# PROC051D_HD_Connector.net
KiCad netlist of a schematic drawn in Altium Designer
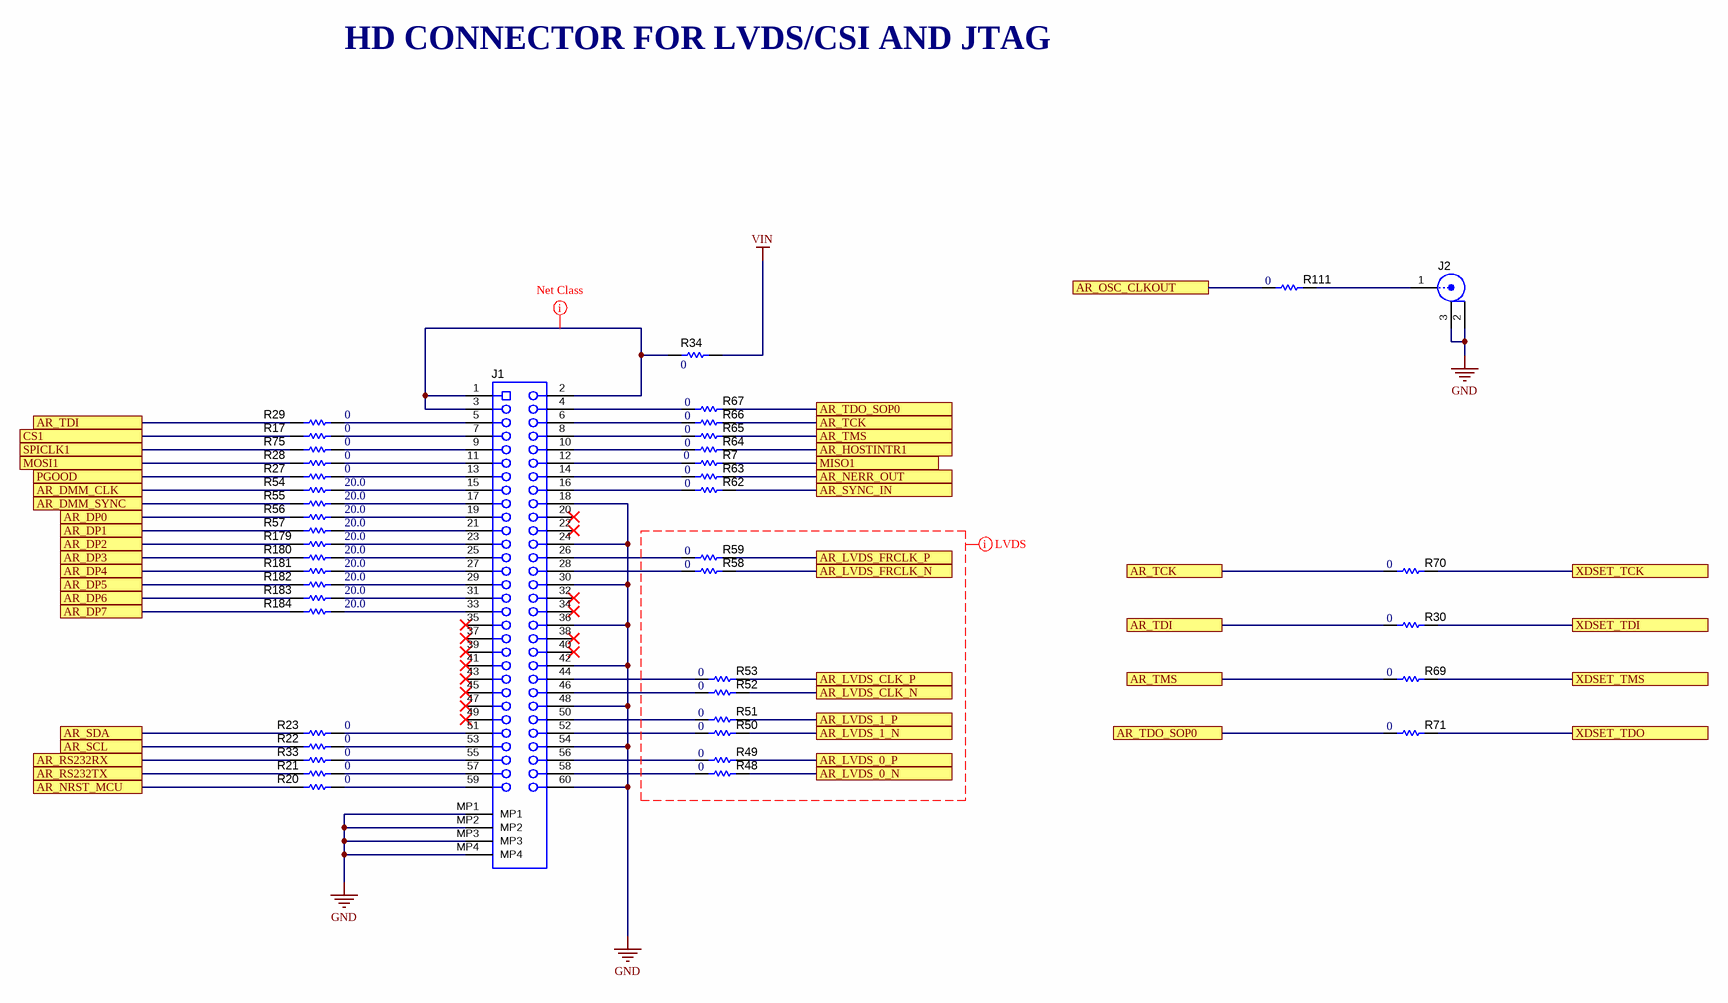
[diagram p0: PROC051D_HD Connector.SchDoc]

(export (version "E")
  (design (tool "Eeschema 10.0.6"))
  (components
    (comp (ref "J1")
      (value "QSH-030-01-L-D-A")
      (footprint "Samtec_QSH-030-01-X-D-A")
      (description "Receptacle, 0.5 mm, 30x2, Gold, TH")
      (fields (field (name "MANUFACTURER") "Samtec") (field (name "PUBLISHER") "Texas Instruments"))
      (libsource (lib "Altium Vault - TI") (part "CMP-0075524-1"))
    )
    (comp (ref "J2")
      (value "128-0711-201")
      (footprint "Johnson_128-0711-201")
      (description "UMC Straight Jack Receptacle, 50 Ohm, Gold, SMT")
      (fields
        (field (name "MANUFACTURER") "Cinch Connectivity")
        (field (name "PUBLISHER") "Texas Instruments")
      )
      (libsource (lib "Altium Vault - TI") (part "CMP-0055788-1"))
    )
    (comp (ref "R7")
      (value "CRCW02010000Z0ED")
      (footprint "0201_Silk")
      (description "RES, 0, 5%, 0.05 W, 0201")
      (fields (field (name "MANUFACTURER") "Vishay-Dale") (field (name "VALUEDISPLAYED") "0"))
      (libsource (lib "Altium Vault - TI") (part "Resistor"))
    )
    (comp (ref "R17")
      (value "CRCW02010000Z0ED")
      (footprint "0201_Silk")
      (description "RES, 0, 5%, 0.05 W, 0201")
      (fields (field (name "MANUFACTURER") "Vishay-Dale") (field (name "VALUEDISPLAYED") "0"))
      (libsource (lib "Altium Vault - TI") (part "Resistor"))
    )
    (comp (ref "R20")
      (value "CRCW02010000Z0ED")
      (footprint "0201_Silk")
      (description "RES, 0, 5%, 0.05 W, 0201")
      (fields (field (name "MANUFACTURER") "Vishay-Dale") (field (name "VALUEDISPLAYED") "0"))
      (libsource (lib "Altium Vault - TI") (part "Resistor"))
    )
    (comp (ref "R21")
      (value "CRCW02010000Z0ED")
      (footprint "0201_Silk")
      (description "RES, 0, 5%, 0.05 W, 0201")
      (fields (field (name "MANUFACTURER") "Vishay-Dale") (field (name "VALUEDISPLAYED") "0"))
      (libsource (lib "Altium Vault - TI") (part "Resistor"))
    )
    (comp (ref "R22")
      (value "CRCW02010000Z0ED")
      (footprint "0201_Silk")
      (description "RES, 0, 5%, 0.05 W, 0201")
      (fields (field (name "MANUFACTURER") "Vishay-Dale") (field (name "VALUEDISPLAYED") "0"))
      (libsource (lib "Altium Vault - TI") (part "Resistor"))
    )
    (comp (ref "R23")
      (value "CRCW02010000Z0ED")
      (footprint "0201_Silk")
      (description "RES, 0, 5%, 0.05 W, 0201")
      (fields (field (name "MANUFACTURER") "Vishay-Dale") (field (name "VALUEDISPLAYED") "0"))
      (libsource (lib "Altium Vault - TI") (part "Resistor"))
    )
    (comp (ref "R27")
      (value "CRCW02010000Z0ED")
      (footprint "0201_Silk")
      (description "RES, 0, 5%, 0.05 W, 0201")
      (fields (field (name "MANUFACTURER") "Vishay-Dale") (field (name "VALUEDISPLAYED") "0"))
      (libsource (lib "Altium Vault - TI") (part "Resistor"))
    )
    (comp (ref "R28")
      (value "CRCW02010000Z0ED")
      (footprint "0201_Silk")
      (description "RES, 0, 5%, 0.05 W, 0201")
      (fields (field (name "MANUFACTURER") "Vishay-Dale") (field (name "VALUEDISPLAYED") "0"))
      (libsource (lib "Altium Vault - TI") (part "Resistor"))
    )
    (comp (ref "R29")
      (value "CRCW02010000Z0ED")
      (footprint "0201_Silk")
      (description "RES, 0, 5%, 0.05 W, 0201")
      (fields (field (name "MANUFACTURER") "Vishay-Dale") (field (name "VALUEDISPLAYED") "0"))
      (libsource (lib "Altium Vault - TI") (part "Resistor"))
    )
    (comp (ref "R30")
      (value "CRCW02010000Z0ED")
      (footprint "0201_Silk")
      (description "RES, 0, 5%, 0.05 W, 0201")
      (fields (field (name "MANUFACTURER") "Vishay-Dale") (field (name "VALUEDISPLAYED") "0"))
      (libsource (lib "Altium Vault - TI") (part "Resistor"))
    )
    (comp (ref "R33")
      (value "CRCW02010000Z0ED")
      (footprint "0201_Silk")
      (description "RES, 0, 5%, 0.05 W, 0201")
      (fields (field (name "MANUFACTURER") "Vishay-Dale") (field (name "VALUEDISPLAYED") "0"))
      (libsource (lib "Altium Vault - TI") (part "Resistor"))
    )
    (comp (ref "R34")
      (value "CRCW20100000Z0EF")
      (footprint "2010")
      (description "RES, 0, 5%, 0.75 W, AEC-Q200 Grade 0, 2010")
      (fields (field (name "MANUFACTURER") "Vishay-Dale") (field (name "VALUEDISPLAYED") "0"))
      (libsource (lib "Altium Vault - TI") (part "Resistor"))
    )
    (comp (ref "R48")
      (value "CRCW02010000Z0ED")
      (footprint "0201_Silk")
      (description "RES, 0, 5%, 0.05 W, 0201")
      (fields (field (name "MANUFACTURER") "Vishay-Dale") (field (name "VALUEDISPLAYED") "0"))
      (libsource (lib "Altium Vault - TI") (part "Resistor"))
    )
    (comp (ref "R49")
      (value "CRCW02010000Z0ED")
      (footprint "0201_Silk")
      (description "RES, 0, 5%, 0.05 W, 0201")
      (fields (field (name "MANUFACTURER") "Vishay-Dale") (field (name "VALUEDISPLAYED") "0"))
      (libsource (lib "Altium Vault - TI") (part "Resistor"))
    )
    (comp (ref "R50")
      (value "CRCW02010000Z0ED")
      (footprint "0201_Silk")
      (description "RES, 0, 5%, 0.05 W, 0201")
      (fields (field (name "MANUFACTURER") "Vishay-Dale") (field (name "VALUEDISPLAYED") "0"))
      (libsource (lib "Altium Vault - TI") (part "Resistor"))
    )
    (comp (ref "R51")
      (value "CRCW02010000Z0ED")
      (footprint "0201_Silk")
      (description "RES, 0, 5%, 0.05 W, 0201")
      (fields (field (name "MANUFACTURER") "Vishay-Dale") (field (name "VALUEDISPLAYED") "0"))
      (libsource (lib "Altium Vault - TI") (part "Resistor"))
    )
    (comp (ref "R52")
      (value "CRCW02010000Z0ED")
      (footprint "0201_Silk")
      (description "RES, 0, 5%, 0.05 W, 0201")
      (fields (field (name "MANUFACTURER") "Vishay-Dale") (field (name "VALUEDISPLAYED") "0"))
      (libsource (lib "Altium Vault - TI") (part "Resistor"))
    )
    (comp (ref "R53")
      (value "CRCW02010000Z0ED")
      (footprint "0201_Silk")
      (description "RES, 0, 5%, 0.05 W, 0201")
      (fields (field (name "MANUFACTURER") "Vishay-Dale") (field (name "VALUEDISPLAYED") "0"))
      (libsource (lib "Altium Vault - TI") (part "Resistor"))
    )
    (comp (ref "R54")
      (value "CRCW020120R0FNED")
      (footprint "0201_033")
      (description "RES, 20.0, 1%, 0.05 W, 0201")
      (fields (field (name "MANUFACTURER") "Vishay-Dale") (field (name "VALUEDISPLAYED") "20.0"))
      (libsource (lib "Altium Vault - TI") (part "Resistor"))
    )
    (comp (ref "R55")
      (value "CRCW020120R0FNED")
      (footprint "0201_033")
      (description "RES, 20.0, 1%, 0.05 W, 0201")
      (fields (field (name "MANUFACTURER") "Vishay-Dale") (field (name "VALUEDISPLAYED") "20.0"))
      (libsource (lib "Altium Vault - TI") (part "Resistor"))
    )
    (comp (ref "R56")
      (value "CRCW020120R0FNED")
      (footprint "0201_033")
      (description "RES, 20.0, 1%, 0.05 W, 0201")
      (fields (field (name "MANUFACTURER") "Vishay-Dale") (field (name "VALUEDISPLAYED") "20.0"))
      (libsource (lib "Altium Vault - TI") (part "Resistor"))
    )
    (comp (ref "R57")
      (value "CRCW020120R0FNED")
      (footprint "0201_033")
      (description "RES, 20.0, 1%, 0.05 W, 0201")
      (fields (field (name "MANUFACTURER") "Vishay-Dale") (field (name "VALUEDISPLAYED") "20.0"))
      (libsource (lib "Altium Vault - TI") (part "Resistor"))
    )
    (comp (ref "R58")
      (value "CRCW02010000Z0ED")
      (footprint "0201_Silk")
      (description "RES, 0, 5%, 0.05 W, 0201")
      (fields (field (name "MANUFACTURER") "Vishay-Dale") (field (name "VALUEDISPLAYED") "0"))
      (libsource (lib "Altium Vault - TI") (part "Resistor"))
    )
    (comp (ref "R59")
      (value "CRCW02010000Z0ED")
      (footprint "0201_Silk")
      (description "RES, 0, 5%, 0.05 W, 0201")
      (fields (field (name "MANUFACTURER") "Vishay-Dale") (field (name "VALUEDISPLAYED") "0"))
      (libsource (lib "Altium Vault - TI") (part "Resistor"))
    )
    (comp (ref "R62")
      (value "CRCW02010000Z0ED")
      (footprint "0201_Silk")
      (description "RES, 0, 5%, 0.05 W, 0201")
      (fields (field (name "MANUFACTURER") "Vishay-Dale") (field (name "VALUEDISPLAYED") "0"))
      (libsource (lib "Altium Vault - TI") (part "Resistor"))
    )
    (comp (ref "R63")
      (value "CRCW02010000Z0ED")
      (footprint "0201_Silk")
      (description "RES, 0, 5%, 0.05 W, 0201")
      (fields (field (name "MANUFACTURER") "Vishay-Dale") (field (name "VALUEDISPLAYED") "0"))
      (libsource (lib "Altium Vault - TI") (part "Resistor"))
    )
    (comp (ref "R64")
      (value "CRCW02010000Z0ED")
      (footprint "0201_Silk")
      (description "RES, 0, 5%, 0.05 W, 0201")
      (fields (field (name "MANUFACTURER") "Vishay-Dale") (field (name "VALUEDISPLAYED") "0"))
      (libsource (lib "Altium Vault - TI") (part "Resistor"))
    )
    (comp (ref "R65")
      (value "CRCW02010000Z0ED")
      (footprint "0201_Silk")
      (description "RES, 0, 5%, 0.05 W, 0201")
      (fields (field (name "MANUFACTURER") "Vishay-Dale") (field (name "VALUEDISPLAYED") "0"))
      (libsource (lib "Altium Vault - TI") (part "Resistor"))
    )
    (comp (ref "R66")
      (value "CRCW02010000Z0ED")
      (footprint "0201_Silk")
      (description "RES, 0, 5%, 0.05 W, 0201")
      (fields (field (name "MANUFACTURER") "Vishay-Dale") (field (name "VALUEDISPLAYED") "0"))
      (libsource (lib "Altium Vault - TI") (part "Resistor"))
    )
    (comp (ref "R67")
      (value "CRCW02010000Z0ED")
      (footprint "0201_Silk")
      (description "RES, 0, 5%, 0.05 W, 0201")
      (fields (field (name "MANUFACTURER") "Vishay-Dale") (field (name "VALUEDISPLAYED") "0"))
      (libsource (lib "Altium Vault - TI") (part "Resistor"))
    )
    (comp (ref "R69")
      (value "CRCW02010000Z0ED")
      (footprint "0201_Silk")
      (description "RES, 0, 5%, 0.05 W, 0201")
      (fields (field (name "MANUFACTURER") "Vishay-Dale") (field (name "VALUEDISPLAYED") "0"))
      (libsource (lib "Altium Vault - TI") (part "Resistor"))
    )
    (comp (ref "R70")
      (value "CRCW02010000Z0ED")
      (footprint "0201_Silk")
      (description "RES, 0, 5%, 0.05 W, 0201")
      (fields (field (name "MANUFACTURER") "Vishay-Dale") (field (name "VALUEDISPLAYED") "0"))
      (libsource (lib "Altium Vault - TI") (part "Resistor"))
    )
    (comp (ref "R71")
      (value "CRCW02010000Z0ED")
      (footprint "0201_Silk")
      (description "RES, 0, 5%, 0.05 W, 0201")
      (fields (field (name "MANUFACTURER") "Vishay-Dale") (field (name "VALUEDISPLAYED") "0"))
      (libsource (lib "Altium Vault - TI") (part "Resistor"))
    )
    (comp (ref "R75")
      (value "CRCW02010000Z0ED")
      (footprint "0201_Silk")
      (description "RES, 0, 5%, 0.05 W, 0201")
      (fields (field (name "MANUFACTURER") "Vishay-Dale") (field (name "VALUEDISPLAYED") "0"))
      (libsource (lib "Altium Vault - TI") (part "Resistor"))
    )
    (comp (ref "R111")
      (value "CRCW02010000Z0ED")
      (footprint "0201_Silk")
      (description "RES, 0, 5%, 0.05 W, 0201")
      (fields (field (name "MANUFACTURER") "Vishay-Dale") (field (name "VALUEDISPLAYED") "0"))
      (libsource (lib "Altium Vault - TI") (part "Resistor"))
    )
    (comp (ref "R179")
      (value "CRCW020120R0FNED")
      (footprint "0201_033")
      (description "RES, 20.0, 1%, 0.05 W, 0201")
      (fields (field (name "MANUFACTURER") "Vishay-Dale") (field (name "VALUEDISPLAYED") "20.0"))
      (libsource (lib "Altium Vault - TI") (part "Resistor"))
    )
    (comp (ref "R180")
      (value "CRCW020120R0FNED")
      (footprint "0201_033")
      (description "RES, 20.0, 1%, 0.05 W, 0201")
      (fields (field (name "MANUFACTURER") "Vishay-Dale") (field (name "VALUEDISPLAYED") "20.0"))
      (libsource (lib "Altium Vault - TI") (part "Resistor"))
    )
    (comp (ref "R181")
      (value "CRCW020120R0FNED")
      (footprint "0201_033")
      (description "RES, 20.0, 1%, 0.05 W, 0201")
      (fields (field (name "MANUFACTURER") "Vishay-Dale") (field (name "VALUEDISPLAYED") "20.0"))
      (libsource (lib "Altium Vault - TI") (part "Resistor"))
    )
    (comp (ref "R182")
      (value "CRCW020120R0FNED")
      (footprint "0201_033")
      (description "RES, 20.0, 1%, 0.05 W, 0201")
      (fields (field (name "MANUFACTURER") "Vishay-Dale") (field (name "VALUEDISPLAYED") "20.0"))
      (libsource (lib "Altium Vault - TI") (part "Resistor"))
    )
    (comp (ref "R183")
      (value "CRCW020120R0FNED")
      (footprint "0201_033")
      (description "RES, 20.0, 1%, 0.05 W, 0201")
      (fields (field (name "MANUFACTURER") "Vishay-Dale") (field (name "VALUEDISPLAYED") "20.0"))
      (libsource (lib "Altium Vault - TI") (part "Resistor"))
    )
    (comp (ref "R184")
      (value "CRCW020120R0FNED")
      (footprint "0201_033")
      (description "RES, 20.0, 1%, 0.05 W, 0201")
      (fields (field (name "MANUFACTURER") "Vishay-Dale") (field (name "VALUEDISPLAYED") "20.0"))
      (libsource (lib "Altium Vault - TI") (part "Resistor"))
    )
  )
  (nets
    (net (code "1") (name "/AR_DMM_CLK") (class "Default")
      (node (ref "R54") (pin "1") (pinfunction "1_1") (pintype "passive"))
    )
    (net (code "2") (name "/AR_DMM_SYNC") (class "Default")
      (node (ref "R55") (pin "1") (pinfunction "1_1") (pintype "passive"))
    )
    (net (code "3") (name "/AR_DP0") (class "Default")
      (node (ref "R56") (pin "1") (pinfunction "1_1") (pintype "passive"))
    )
    (net (code "4") (name "/AR_DP1") (class "Default")
      (node (ref "R57") (pin "1") (pinfunction "1_1") (pintype "passive"))
    )
    (net (code "5") (name "/AR_DP2") (class "Default")
      (node (ref "R179") (pin "1") (pinfunction "1_1") (pintype "passive"))
    )
    (net (code "6") (name "/AR_DP3") (class "Default")
      (node (ref "R180") (pin "1") (pinfunction "1_1") (pintype "passive"))
    )
    (net (code "7") (name "/AR_DP4") (class "Default")
      (node (ref "R181") (pin "1") (pinfunction "1_1") (pintype "passive"))
    )
    (net (code "8") (name "/AR_DP5") (class "Default")
      (node (ref "R182") (pin "1") (pinfunction "1_1") (pintype "passive"))
    )
    (net (code "9") (name "/AR_DP6") (class "Default")
      (node (ref "R183") (pin "1") (pinfunction "1_1") (pintype "passive"))
    )
    (net (code "10") (name "/AR_DP7") (class "Default")
      (node (ref "R184") (pin "1") (pinfunction "1_1") (pintype "passive"))
    )
    (net (code "11") (name "/AR_HOSTINTR1") (class "Default")
      (node (ref "R64") (pin "2") (pinfunction "2_2") (pintype "passive"))
    )
    (net (code "12") (name "/AR_LVDS_0_N") (class "Default")
      (node (ref "R48") (pin "2") (pinfunction "2_2") (pintype "passive"))
    )
    (net (code "13") (name "/AR_LVDS_0_P") (class "Default")
      (node (ref "R49") (pin "2") (pinfunction "2_2") (pintype "passive"))
    )
    (net (code "14") (name "/AR_LVDS_1_N") (class "Default")
      (node (ref "R50") (pin "2") (pinfunction "2_2") (pintype "passive"))
    )
    (net (code "15") (name "/AR_LVDS_1_P") (class "Default")
      (node (ref "R51") (pin "2") (pinfunction "2_2") (pintype "passive"))
    )
    (net (code "16") (name "/AR_LVDS_CLK_N") (class "Default")
      (node (ref "R52") (pin "2") (pinfunction "2_2") (pintype "passive"))
    )
    (net (code "17") (name "/AR_LVDS_CLK_P") (class "Default")
      (node (ref "R53") (pin "2") (pinfunction "2_2") (pintype "passive"))
    )
    (net (code "18") (name "/AR_LVDS_FRCLK_N") (class "Default")
      (node (ref "R58") (pin "2") (pinfunction "2_2") (pintype "passive"))
    )
    (net (code "19") (name "/AR_LVDS_FRCLK_P") (class "Default")
      (node (ref "R59") (pin "2") (pinfunction "2_2") (pintype "passive"))
    )
    (net (code "20") (name "/AR_NERR_OUT") (class "Default")
      (node (ref "R63") (pin "2") (pinfunction "2_2") (pintype "passive"))
    )
    (net (code "21") (name "/AR_NRST_MCU") (class "Default")
      (node (ref "R20") (pin "1") (pinfunction "1_1") (pintype "passive"))
    )
    (net (code "22") (name "/AR_OSC_CLKOUT") (class "Default")
      (node (ref "R111") (pin "1") (pinfunction "1_1") (pintype "passive"))
    )
    (net (code "23") (name "/AR_RS232RX") (class "Default")
      (node (ref "R33") (pin "1") (pinfunction "1_1") (pintype "passive"))
    )
    (net (code "24") (name "/AR_RS232TX") (class "Default")
      (node (ref "R21") (pin "1") (pinfunction "1_1") (pintype "passive"))
    )
    (net (code "25") (name "/AR_SCL") (class "Default")
      (node (ref "R22") (pin "1") (pinfunction "1_1") (pintype "passive"))
    )
    (net (code "26") (name "/AR_SDA") (class "Default")
      (node (ref "R23") (pin "1") (pinfunction "1_1") (pintype "passive"))
    )
    (net (code "27") (name "/AR_SYNC_IN") (class "Default")
      (node (ref "R62") (pin "2") (pinfunction "2_2") (pintype "passive"))
    )
    (net (code "28") (name "/AR_TCK") (class "Default")
      (node (ref "R66") (pin "2") (pinfunction "2_2") (pintype "passive"))
      (node (ref "R70") (pin "1") (pinfunction "1_1") (pintype "passive"))
    )
    (net (code "29") (name "/AR_TDI") (class "Default")
      (node (ref "R29") (pin "1") (pinfunction "1_1") (pintype "passive"))
      (node (ref "R30") (pin "1") (pinfunction "1_1") (pintype "passive"))
    )
    (net (code "30") (name "/AR_TDO_SOP0") (class "Default")
      (node (ref "R67") (pin "2") (pinfunction "2_2") (pintype "passive"))
      (node (ref "R71") (pin "1") (pinfunction "1_1") (pintype "passive"))
    )
    (net (code "31") (name "/AR_TMS") (class "Default")
      (node (ref "R65") (pin "2") (pinfunction "2_2") (pintype "passive"))
      (node (ref "R69") (pin "1") (pinfunction "1_1") (pintype "passive"))
    )
    (net (code "32") (name "/CS1") (class "Default")
      (node (ref "R17") (pin "1") (pinfunction "1_1") (pintype "passive"))
    )
    (net (code "33") (name "/MISO1") (class "Default")
      (node (ref "R7") (pin "2") (pinfunction "2_2") (pintype "passive"))
    )
    (net (code "34") (name "/MOSI1") (class "Default")
      (node (ref "R28") (pin "1") (pinfunction "1_1") (pintype "passive"))
    )
    (net (code "35") (name "/PGOOD") (class "Default")
      (node (ref "R27") (pin "1") (pinfunction "1_1") (pintype "passive"))
    )
    (net (code "36") (name "/SPICLK1") (class "Default")
      (node (ref "R75") (pin "1") (pinfunction "1_1") (pintype "passive"))
    )
    (net (code "37") (name "/XDSET_TCK") (class "Default")
      (node (ref "R70") (pin "2") (pinfunction "2_2") (pintype "passive"))
    )
    (net (code "38") (name "/XDSET_TDI") (class "Default")
      (node (ref "R30") (pin "2") (pinfunction "2_2") (pintype "passive"))
    )
    (net (code "39") (name "/XDSET_TDO") (class "Default")
      (node (ref "R71") (pin "2") (pinfunction "2_2") (pintype "passive"))
    )
    (net (code "40") (name "/XDSET_TMS") (class "Default")
      (node (ref "R69") (pin "2") (pinfunction "2_2") (pintype "passive"))
    )
    (net (code "41") (name "GND") (class "Default")
      (node (ref "J1") (pin "18") (pinfunction "18_18") (pintype "passive"))
      (node (ref "J1") (pin "24") (pinfunction "24_24") (pintype "passive"))
      (node (ref "J1") (pin "30") (pinfunction "30_30") (pintype "passive"))
      (node (ref "J1") (pin "36") (pinfunction "36_36") (pintype "passive"))
      (node (ref "J1") (pin "42") (pinfunction "42_42") (pintype "passive"))
      (node (ref "J1") (pin "48") (pinfunction "48_48") (pintype "passive"))
      (node (ref "J1") (pin "54") (pinfunction "54_54") (pintype "passive"))
      (node (ref "J1") (pin "60") (pinfunction "60_60") (pintype "passive"))
      (node (ref "J1") (pin "MP1") (pinfunction "MP1_MP1") (pintype "passive"))
      (node (ref "J1") (pin "MP2") (pinfunction "MP2_MP2") (pintype "passive"))
      (node (ref "J1") (pin "MP3") (pinfunction "MP3_MP3") (pintype "passive"))
      (node (ref "J1") (pin "MP4") (pinfunction "MP4_MP4") (pintype "passive"))
      (node (ref "J2") (pin "2") (pinfunction "2_2") (pintype "passive"))
      (node (ref "J2") (pin "3") (pinfunction "3_3") (pintype "passive"))
    )
    (net (code "42") (name "Net-(J1-Pad1)") (class "Default")
      (node (ref "J1") (pin "1") (pinfunction "1_1") (pintype "passive"))
      (node (ref "J1") (pin "2") (pinfunction "2_2") (pintype "passive"))
      (node (ref "J1") (pin "3") (pinfunction "3_3") (pintype "passive"))
      (node (ref "R34") (pin "1") (pinfunction "1_1") (pintype "passive"))
    )
    (net (code "43") (name "Net-(J1-Pad4)") (class "Default")
      (node (ref "J1") (pin "4") (pinfunction "4_4") (pintype "passive"))
      (node (ref "R67") (pin "1") (pinfunction "1_1") (pintype "passive"))
    )
    (net (code "44") (name "Net-(J1-Pad5)") (class "Default")
      (node (ref "J1") (pin "5") (pinfunction "5_5") (pintype "passive"))
      (node (ref "R29") (pin "2") (pinfunction "2_2") (pintype "passive"))
    )
    (net (code "45") (name "Net-(J1-Pad6)") (class "Default")
      (node (ref "J1") (pin "6") (pinfunction "6_6") (pintype "passive"))
      (node (ref "R66") (pin "1") (pinfunction "1_1") (pintype "passive"))
    )
    (net (code "46") (name "Net-(J1-Pad7)") (class "Default")
      (node (ref "J1") (pin "7") (pinfunction "7_7") (pintype "passive"))
      (node (ref "R17") (pin "2") (pinfunction "2_2") (pintype "passive"))
    )
    (net (code "47") (name "Net-(J1-Pad8)") (class "Default")
      (node (ref "J1") (pin "8") (pinfunction "8_8") (pintype "passive"))
      (node (ref "R65") (pin "1") (pinfunction "1_1") (pintype "passive"))
    )
    (net (code "48") (name "Net-(J1-Pad9)") (class "Default")
      (node (ref "J1") (pin "9") (pinfunction "9_9") (pintype "passive"))
      (node (ref "R75") (pin "2") (pinfunction "2_2") (pintype "passive"))
    )
    (net (code "49") (name "Net-(J1-Pad10)") (class "Default")
      (node (ref "J1") (pin "10") (pinfunction "10_10") (pintype "passive"))
      (node (ref "R64") (pin "1") (pinfunction "1_1") (pintype "passive"))
    )
    (net (code "50") (name "Net-(J1-Pad11)") (class "Default")
      (node (ref "J1") (pin "11") (pinfunction "11_11") (pintype "passive"))
      (node (ref "R28") (pin "2") (pinfunction "2_2") (pintype "passive"))
    )
    (net (code "51") (name "Net-(J1-Pad12)") (class "Default")
      (node (ref "J1") (pin "12") (pinfunction "12_12") (pintype "passive"))
      (node (ref "R7") (pin "1") (pinfunction "1_1") (pintype "passive"))
    )
    (net (code "52") (name "Net-(J1-Pad13)") (class "Default")
      (node (ref "J1") (pin "13") (pinfunction "13_13") (pintype "passive"))
      (node (ref "R27") (pin "2") (pinfunction "2_2") (pintype "passive"))
    )
    (net (code "53") (name "Net-(J1-Pad14)") (class "Default")
      (node (ref "J1") (pin "14") (pinfunction "14_14") (pintype "passive"))
      (node (ref "R63") (pin "1") (pinfunction "1_1") (pintype "passive"))
    )
    (net (code "54") (name "Net-(J1-Pad15)") (class "Default")
      (node (ref "J1") (pin "15") (pinfunction "15_15") (pintype "passive"))
      (node (ref "R54") (pin "2") (pinfunction "2_2") (pintype "passive"))
    )
    (net (code "55") (name "Net-(J1-Pad16)") (class "Default")
      (node (ref "J1") (pin "16") (pinfunction "16_16") (pintype "passive"))
      (node (ref "R62") (pin "1") (pinfunction "1_1") (pintype "passive"))
    )
    (net (code "56") (name "Net-(J1-Pad17)") (class "Default")
      (node (ref "J1") (pin "17") (pinfunction "17_17") (pintype "passive"))
      (node (ref "R55") (pin "2") (pinfunction "2_2") (pintype "passive"))
    )
    (net (code "57") (name "Net-(J1-Pad19)") (class "Default")
      (node (ref "J1") (pin "19") (pinfunction "19_19") (pintype "passive"))
      (node (ref "R56") (pin "2") (pinfunction "2_2") (pintype "passive"))
    )
    (net (code "58") (name "Net-(J1-Pad21)") (class "Default")
      (node (ref "J1") (pin "21") (pinfunction "21_21") (pintype "passive"))
      (node (ref "R57") (pin "2") (pinfunction "2_2") (pintype "passive"))
    )
    (net (code "59") (name "Net-(J1-Pad23)") (class "Default")
      (node (ref "J1") (pin "23") (pinfunction "23_23") (pintype "passive"))
      (node (ref "R179") (pin "2") (pinfunction "2_2") (pintype "passive"))
    )
    (net (code "60") (name "Net-(J1-Pad25)") (class "Default")
      (node (ref "J1") (pin "25") (pinfunction "25_25") (pintype "passive"))
      (node (ref "R180") (pin "2") (pinfunction "2_2") (pintype "passive"))
    )
    (net (code "61") (name "Net-(J1-Pad26)") (class "Default")
      (node (ref "J1") (pin "26") (pinfunction "26_26") (pintype "passive"))
      (node (ref "R59") (pin "1") (pinfunction "1_1") (pintype "passive"))
    )
    (net (code "62") (name "Net-(J1-Pad27)") (class "Default")
      (node (ref "J1") (pin "27") (pinfunction "27_27") (pintype "passive"))
      (node (ref "R181") (pin "2") (pinfunction "2_2") (pintype "passive"))
    )
    (net (code "63") (name "Net-(J1-Pad28)") (class "Default")
      (node (ref "J1") (pin "28") (pinfunction "28_28") (pintype "passive"))
      (node (ref "R58") (pin "1") (pinfunction "1_1") (pintype "passive"))
    )
    (net (code "64") (name "Net-(J1-Pad29)") (class "Default")
      (node (ref "J1") (pin "29") (pinfunction "29_29") (pintype "passive"))
      (node (ref "R182") (pin "2") (pinfunction "2_2") (pintype "passive"))
    )
    (net (code "65") (name "Net-(J1-Pad31)") (class "Default")
      (node (ref "J1") (pin "31") (pinfunction "31_31") (pintype "passive"))
      (node (ref "R183") (pin "2") (pinfunction "2_2") (pintype "passive"))
    )
    (net (code "66") (name "Net-(J1-Pad33)") (class "Default")
      (node (ref "J1") (pin "33") (pinfunction "33_33") (pintype "passive"))
      (node (ref "R184") (pin "2") (pinfunction "2_2") (pintype "passive"))
    )
    (net (code "67") (name "Net-(J1-Pad44)") (class "Default")
      (node (ref "J1") (pin "44") (pinfunction "44_44") (pintype "passive"))
      (node (ref "R53") (pin "1") (pinfunction "1_1") (pintype "passive"))
    )
    (net (code "68") (name "Net-(J1-Pad46)") (class "Default")
      (node (ref "J1") (pin "46") (pinfunction "46_46") (pintype "passive"))
      (node (ref "R52") (pin "1") (pinfunction "1_1") (pintype "passive"))
    )
    (net (code "69") (name "Net-(J1-Pad50)") (class "Default")
      (node (ref "J1") (pin "50") (pinfunction "50_50") (pintype "passive"))
      (node (ref "R51") (pin "1") (pinfunction "1_1") (pintype "passive"))
    )
    (net (code "70") (name "Net-(J1-Pad51)") (class "Default")
      (node (ref "J1") (pin "51") (pinfunction "51_51") (pintype "passive"))
      (node (ref "R23") (pin "2") (pinfunction "2_2") (pintype "passive"))
    )
    (net (code "71") (name "Net-(J1-Pad52)") (class "Default")
      (node (ref "J1") (pin "52") (pinfunction "52_52") (pintype "passive"))
      (node (ref "R50") (pin "1") (pinfunction "1_1") (pintype "passive"))
    )
    (net (code "72") (name "Net-(J1-Pad53)") (class "Default")
      (node (ref "J1") (pin "53") (pinfunction "53_53") (pintype "passive"))
      (node (ref "R22") (pin "2") (pinfunction "2_2") (pintype "passive"))
    )
    (net (code "73") (name "Net-(J1-Pad55)") (class "Default")
      (node (ref "J1") (pin "55") (pinfunction "55_55") (pintype "passive"))
      (node (ref "R33") (pin "2") (pinfunction "2_2") (pintype "passive"))
    )
    (net (code "74") (name "Net-(J1-Pad56)") (class "Default")
      (node (ref "J1") (pin "56") (pinfunction "56_56") (pintype "passive"))
      (node (ref "R49") (pin "1") (pinfunction "1_1") (pintype "passive"))
    )
    (net (code "75") (name "Net-(J1-Pad57)") (class "Default")
      (node (ref "J1") (pin "57") (pinfunction "57_57") (pintype "passive"))
      (node (ref "R21") (pin "2") (pinfunction "2_2") (pintype "passive"))
    )
    (net (code "76") (name "Net-(J1-Pad58)") (class "Default")
      (node (ref "J1") (pin "58") (pinfunction "58_58") (pintype "passive"))
      (node (ref "R48") (pin "1") (pinfunction "1_1") (pintype "passive"))
    )
    (net (code "77") (name "Net-(J1-Pad59)") (class "Default")
      (node (ref "J1") (pin "59") (pinfunction "59_59") (pintype "passive"))
      (node (ref "R20") (pin "2") (pinfunction "2_2") (pintype "passive"))
    )
    (net (code "78") (name "Net-(J2-Pad1)") (class "Default")
      (node (ref "J2") (pin "1") (pinfunction "1_1") (pintype "passive"))
      (node (ref "R111") (pin "2") (pinfunction "2_2") (pintype "passive"))
    )
    (net (code "79") (name "VIN") (class "Default")
      (node (ref "R34") (pin "2") (pinfunction "2_2") (pintype "passive"))
    )
    (net (code "80") (name "unconnected-(J1-Pad20)") (class "Default")
      (node (ref "J1") (pin "20") (pinfunction "20_20") (pintype "passive+no_connect"))
    )
    (net (code "81") (name "unconnected-(J1-Pad22)") (class "Default")
      (node (ref "J1") (pin "22") (pinfunction "22_22") (pintype "passive+no_connect"))
    )
    (net (code "82") (name "unconnected-(J1-Pad32)") (class "Default")
      (node (ref "J1") (pin "32") (pinfunction "32_32") (pintype "passive+no_connect"))
    )
    (net (code "83") (name "unconnected-(J1-Pad34)") (class "Default")
      (node (ref "J1") (pin "34") (pinfunction "34_34") (pintype "passive+no_connect"))
    )
    (net (code "84") (name "unconnected-(J1-Pad35)") (class "Default")
      (node (ref "J1") (pin "35") (pinfunction "35_35") (pintype "passive+no_connect"))
    )
    (net (code "85") (name "unconnected-(J1-Pad37)") (class "Default")
      (node (ref "J1") (pin "37") (pinfunction "37_37") (pintype "passive+no_connect"))
    )
    (net (code "86") (name "unconnected-(J1-Pad38)") (class "Default")
      (node (ref "J1") (pin "38") (pinfunction "38_38") (pintype "passive+no_connect"))
    )
    (net (code "87") (name "unconnected-(J1-Pad39)") (class "Default")
      (node (ref "J1") (pin "39") (pinfunction "39_39") (pintype "passive+no_connect"))
    )
    (net (code "88") (name "unconnected-(J1-Pad40)") (class "Default")
      (node (ref "J1") (pin "40") (pinfunction "40_40") (pintype "passive+no_connect"))
    )
    (net (code "89") (name "unconnected-(J1-Pad41)") (class "Default")
      (node (ref "J1") (pin "41") (pinfunction "41_41") (pintype "passive+no_connect"))
    )
    (net (code "90") (name "unconnected-(J1-Pad43)") (class "Default")
      (node (ref "J1") (pin "43") (pinfunction "43_43") (pintype "passive+no_connect"))
    )
    (net (code "91") (name "unconnected-(J1-Pad45)") (class "Default")
      (node (ref "J1") (pin "45") (pinfunction "45_45") (pintype "passive+no_connect"))
    )
    (net (code "92") (name "unconnected-(J1-Pad47)") (class "Default")
      (node (ref "J1") (pin "47") (pinfunction "47_47") (pintype "passive+no_connect"))
    )
    (net (code "93") (name "unconnected-(J1-Pad49)") (class "Default")
      (node (ref "J1") (pin "49") (pinfunction "49_49") (pintype "passive+no_connect"))
    )
  )
)
